# DOUT.net
KiCad netlist of a schematic drawn in EAGLE
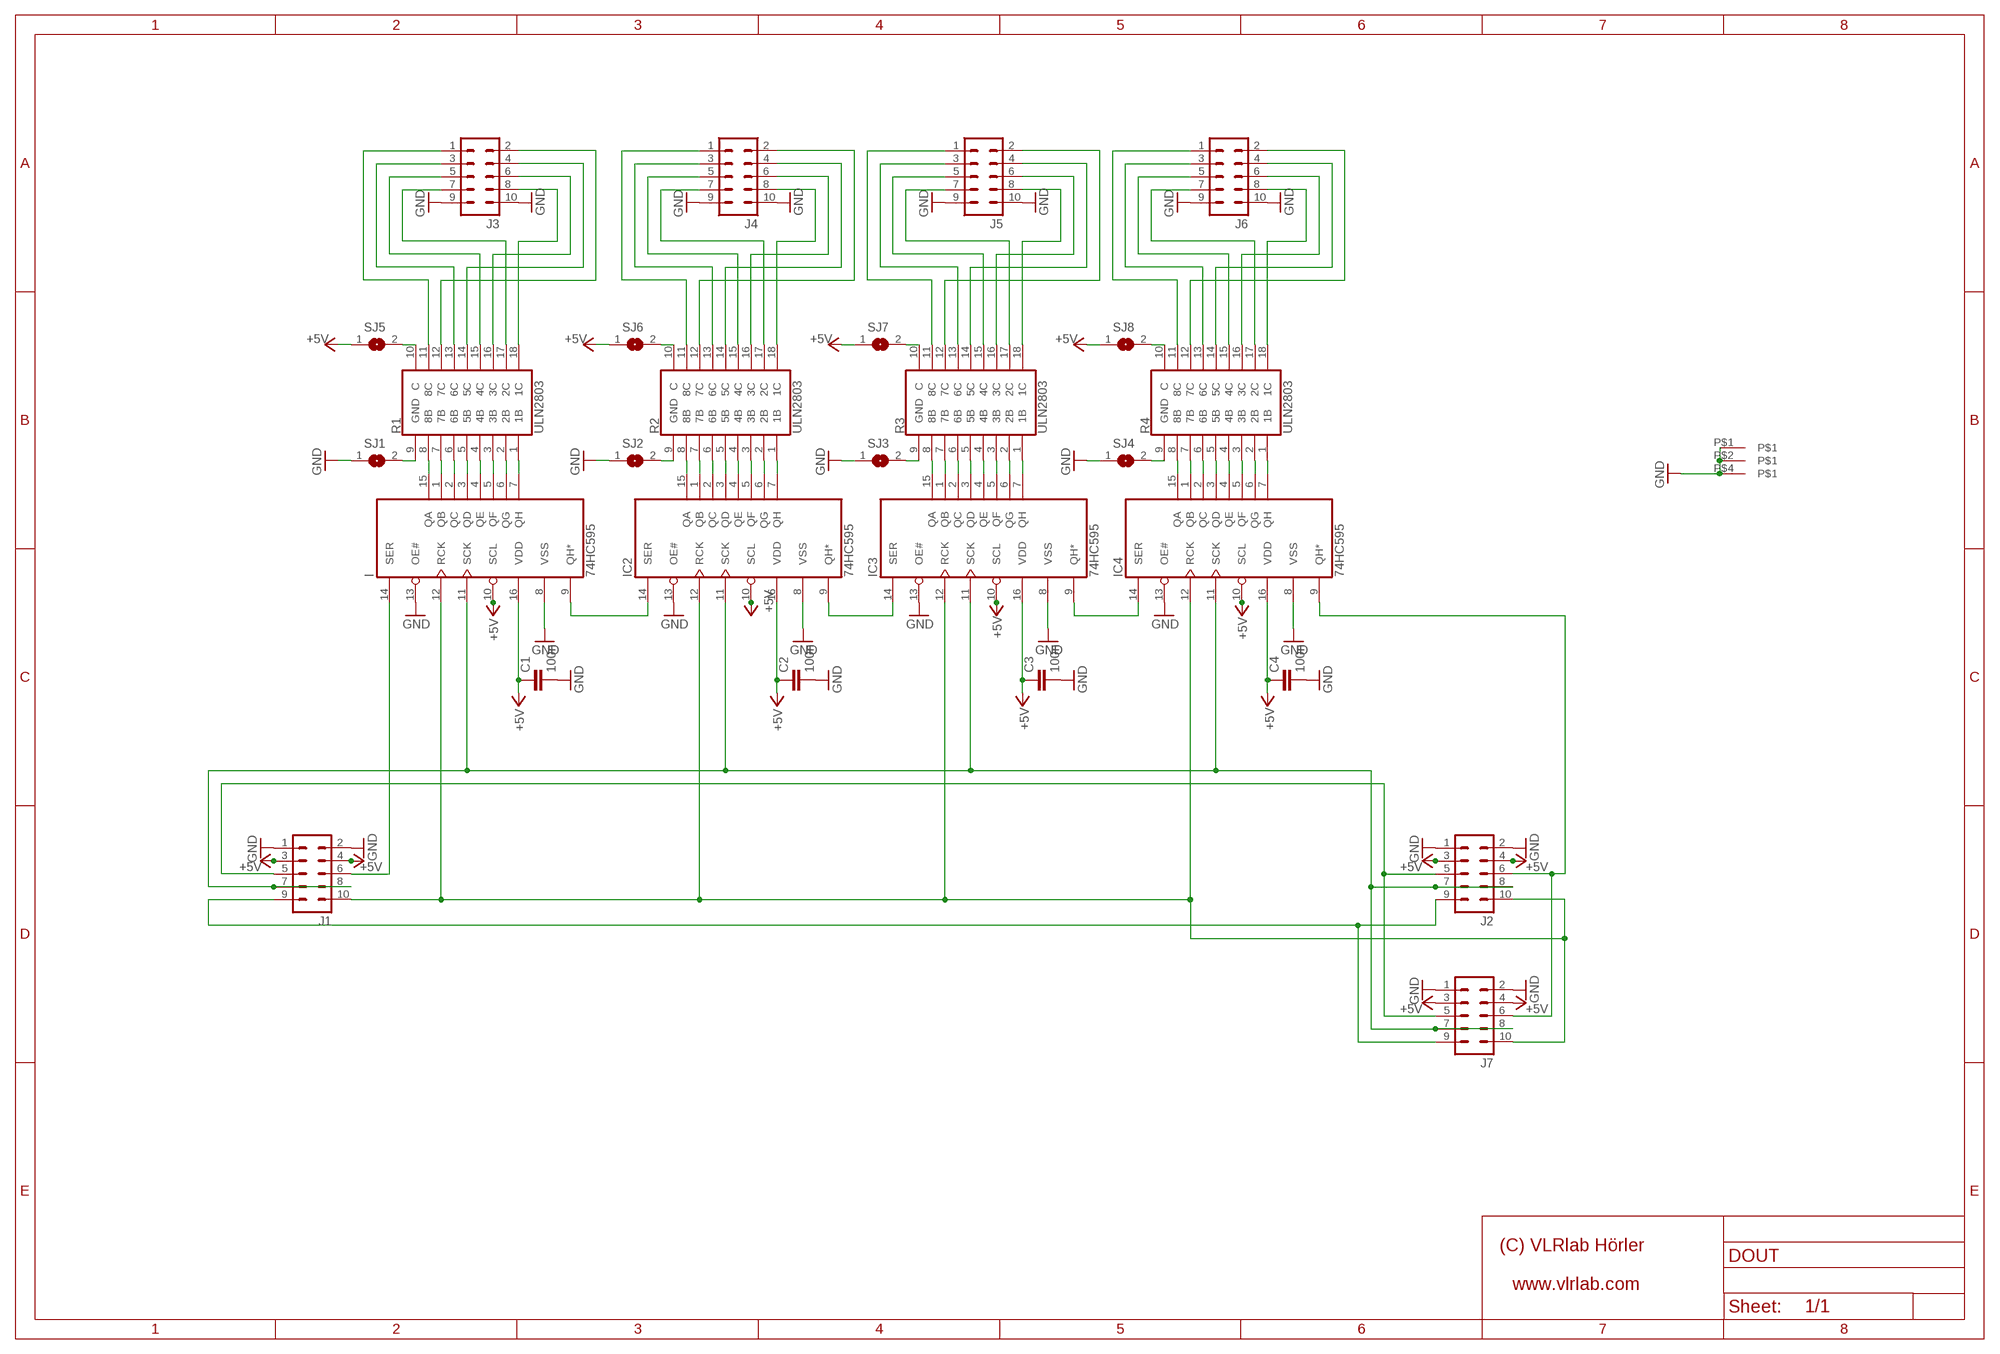
[diagram p0: schematic, sheet 1]

(export (version "E")
  (design (tool "Eeschema 10.0.6"))
  (components
    (comp (ref "C1")
      (value "100n")
      (footprint "eagle-import:C025-025X050")
      (libsource (lib "eagle-import") (part "C-EU025-025X050"))
    )
    (comp (ref "C2")
      (value "100n")
      (footprint "eagle-import:C025-025X050")
      (libsource (lib "eagle-import") (part "C-EU025-025X050"))
    )
    (comp (ref "C3")
      (value "100n")
      (footprint "eagle-import:C025-025X050")
      (libsource (lib "eagle-import") (part "C-EU025-025X050"))
    )
    (comp (ref "C4")
      (value "100n")
      (footprint "eagle-import:C025-025X050")
      (libsource (lib "eagle-import") (part "C-EU025-025X050"))
    )
    (comp (ref "I")
      (value "74HC595")
      (footprint "eagle-import:DIL16")
      (libsource (lib "eagle-import") (part "74HC595DIP16"))
    )
    (comp (ref "IC2")
      (value "74HC595")
      (footprint "eagle-import:DIL16")
      (libsource (lib "eagle-import") (part "74HC595DIP16"))
    )
    (comp (ref "IC3")
      (value "74HC595")
      (footprint "eagle-import:DIL16")
      (libsource (lib "eagle-import") (part "74HC595DIP16"))
    )
    (comp (ref "IC4")
      (value "74HC595")
      (footprint "eagle-import:DIL16")
      (libsource (lib "eagle-import") (part "74HC595DIP16"))
    )
    (comp (ref "J1")
      (value "ML10")
      (footprint "eagle-import:ML10")
      (libsource (lib "eagle-import") (part "ML10"))
    )
    (comp (ref "J2")
      (value "ML10")
      (footprint "eagle-import:ML10")
      (libsource (lib "eagle-import") (part "ML10"))
    )
    (comp (ref "J3")
      (value "ML10")
      (footprint "eagle-import:ML10")
      (libsource (lib "eagle-import") (part "ML10"))
    )
    (comp (ref "J4")
      (value "ML10")
      (footprint "eagle-import:ML10")
      (libsource (lib "eagle-import") (part "ML10"))
    )
    (comp (ref "J5")
      (value "ML10")
      (footprint "eagle-import:ML10")
      (libsource (lib "eagle-import") (part "ML10"))
    )
    (comp (ref "J6")
      (value "ML10")
      (footprint "eagle-import:ML10")
      (libsource (lib "eagle-import") (part "ML10"))
    )
    (comp (ref "J7")
      (value "ML10")
      (footprint "eagle-import:ML10")
      (libsource (lib "eagle-import") (part "ML10"))
    )
    (comp (ref "R1")
      (value "ULN2803")
      (footprint "eagle-import:DIL18")
      (libsource (lib "eagle-import") (part "ULN2803"))
    )
    (comp (ref "R2")
      (value "ULN2803")
      (footprint "eagle-import:DIL18")
      (libsource (lib "eagle-import") (part "ULN2803"))
    )
    (comp (ref "R3")
      (value "ULN2803")
      (footprint "eagle-import:DIL18")
      (libsource (lib "eagle-import") (part "ULN2803"))
    )
    (comp (ref "R4")
      (value "ULN2803")
      (footprint "eagle-import:DIL18")
      (libsource (lib "eagle-import") (part "ULN2803"))
    )
    (comp (ref "SJ1") (value "SJ") (footprint "eagle-import:SJ") (libsource (lib "eagle-import") (part "SJ")))
    (comp (ref "SJ2") (value "SJ") (footprint "eagle-import:SJ") (libsource (lib "eagle-import") (part "SJ")))
    (comp (ref "SJ3") (value "SJ") (footprint "eagle-import:SJ") (libsource (lib "eagle-import") (part "SJ")))
    (comp (ref "SJ4") (value "SJ") (footprint "eagle-import:SJ") (libsource (lib "eagle-import") (part "SJ")))
    (comp (ref "SJ5") (value "SJ") (footprint "eagle-import:SJ") (libsource (lib "eagle-import") (part "SJ")))
    (comp (ref "SJ6") (value "SJ") (footprint "eagle-import:SJ") (libsource (lib "eagle-import") (part "SJ")))
    (comp (ref "SJ7") (value "SJ") (footprint "eagle-import:SJ") (libsource (lib "eagle-import") (part "SJ")))
    (comp (ref "SJ8") (value "SJ") (footprint "eagle-import:SJ") (libsource (lib "eagle-import") (part "SJ")))
    (comp (ref "U$7")
      (value "MIDIBOX_HALF")
      (footprint "eagle-import:MIDIBOX14X6")
      (libsource (lib "eagle-import") (part "MIDIBOX_HALF"))
    )
  )
  (nets
    (net (code "1") (name "+5V") (class "Default")
      (node (ref "C1") (pin "1") (pinfunction "1_1") (pintype "passive"))
      (node (ref "C2") (pin "1") (pinfunction "1_1") (pintype "passive"))
      (node (ref "C3") (pin "1") (pinfunction "1_1") (pintype "passive"))
      (node (ref "C4") (pin "1") (pinfunction "1_1") (pintype "passive"))
      (node (ref "I") (pin "10") (pinfunction "SCL_10") (pintype "input"))
      (node (ref "I") (pin "16") (pinfunction "VDD_16") (pintype "power_in"))
      (node (ref "IC2") (pin "10") (pinfunction "SCL_10") (pintype "input"))
      (node (ref "IC2") (pin "16") (pinfunction "VDD_16") (pintype "power_in"))
      (node (ref "IC3") (pin "10") (pinfunction "SCL_10") (pintype "input"))
      (node (ref "IC3") (pin "16") (pinfunction "VDD_16") (pintype "power_in"))
      (node (ref "IC4") (pin "10") (pinfunction "SCL_10") (pintype "input"))
      (node (ref "IC4") (pin "16") (pinfunction "VDD_16") (pintype "power_in"))
      (node (ref "J1") (pin "3") (pinfunction "3_3") (pintype "passive"))
      (node (ref "J1") (pin "4") (pinfunction "4_4") (pintype "passive"))
      (node (ref "J2") (pin "3") (pinfunction "3_3") (pintype "passive"))
      (node (ref "J2") (pin "4") (pinfunction "4_4") (pintype "passive"))
      (node (ref "J7") (pin "3") (pinfunction "3_3") (pintype "passive"))
      (node (ref "J7") (pin "4") (pinfunction "4_4") (pintype "passive"))
      (node (ref "SJ5") (pin "1") (pinfunction "1_1") (pintype "passive"))
      (node (ref "SJ6") (pin "1") (pinfunction "1_1") (pintype "passive"))
      (node (ref "SJ7") (pin "1") (pinfunction "1_1") (pintype "passive"))
      (node (ref "SJ8") (pin "1") (pinfunction "1_1") (pintype "passive"))
    )
    (net (code "2") (name "GND") (class "Default")
      (node (ref "C1") (pin "2") (pinfunction "2_2") (pintype "passive"))
      (node (ref "C2") (pin "2") (pinfunction "2_2") (pintype "passive"))
      (node (ref "C3") (pin "2") (pinfunction "2_2") (pintype "passive"))
      (node (ref "C4") (pin "2") (pinfunction "2_2") (pintype "passive"))
      (node (ref "I") (pin "13") (pinfunction "OE#_13") (pintype "input"))
      (node (ref "I") (pin "8") (pinfunction "VSS_8") (pintype "power_in"))
      (node (ref "IC2") (pin "13") (pinfunction "OE#_13") (pintype "input"))
      (node (ref "IC2") (pin "8") (pinfunction "VSS_8") (pintype "power_in"))
      (node (ref "IC3") (pin "13") (pinfunction "OE#_13") (pintype "input"))
      (node (ref "IC3") (pin "8") (pinfunction "VSS_8") (pintype "power_in"))
      (node (ref "IC4") (pin "13") (pinfunction "OE#_13") (pintype "input"))
      (node (ref "IC4") (pin "8") (pinfunction "VSS_8") (pintype "power_in"))
      (node (ref "J1") (pin "1") (pinfunction "1_1") (pintype "passive"))
      (node (ref "J1") (pin "2") (pinfunction "2_2") (pintype "passive"))
      (node (ref "J2") (pin "1") (pinfunction "1_1") (pintype "passive"))
      (node (ref "J2") (pin "2") (pinfunction "2_2") (pintype "passive"))
      (node (ref "J3") (pin "10") (pinfunction "10_10") (pintype "passive"))
      (node (ref "J3") (pin "9") (pinfunction "9_9") (pintype "passive"))
      (node (ref "J4") (pin "10") (pinfunction "10_10") (pintype "passive"))
      (node (ref "J4") (pin "9") (pinfunction "9_9") (pintype "passive"))
      (node (ref "J5") (pin "10") (pinfunction "10_10") (pintype "passive"))
      (node (ref "J5") (pin "9") (pinfunction "9_9") (pintype "passive"))
      (node (ref "J6") (pin "10") (pinfunction "10_10") (pintype "passive"))
      (node (ref "J6") (pin "9") (pinfunction "9_9") (pintype "passive"))
      (node (ref "J7") (pin "1") (pinfunction "1_1") (pintype "passive"))
      (node (ref "J7") (pin "2") (pinfunction "2_2") (pintype "passive"))
      (node (ref "SJ1") (pin "1") (pinfunction "1_1") (pintype "passive"))
      (node (ref "SJ2") (pin "1") (pinfunction "1_1") (pintype "passive"))
      (node (ref "SJ3") (pin "1") (pinfunction "1_1") (pintype "passive"))
      (node (ref "SJ4") (pin "1") (pinfunction "1_1") (pintype "passive"))
      (node (ref "U$7") (pin "P$1") (pinfunction "P$1_P$1") (pintype "bidirectional"))
      (node (ref "U$7") (pin "P$2") (pinfunction "P$1_P$2") (pintype "bidirectional"))
      (node (ref "U$7") (pin "P$4") (pinfunction "P$1_P$4") (pintype "bidirectional"))
    )
    (net (code "3") (name "Net-(I-QA)") (class "Default")
      (node (ref "I") (pin "15") (pinfunction "QA_15") (pintype "tri_state"))
      (node (ref "R1") (pin "8") (pinfunction "8B_8") (pintype "input"))
    )
    (net (code "4") (name "Net-(I-QB)") (class "Default")
      (node (ref "I") (pin "1") (pinfunction "QB_1") (pintype "tri_state"))
      (node (ref "R1") (pin "7") (pinfunction "7B_7") (pintype "input"))
    )
    (net (code "5") (name "Net-(I-QC)") (class "Default")
      (node (ref "I") (pin "2") (pinfunction "QC_2") (pintype "tri_state"))
      (node (ref "R1") (pin "6") (pinfunction "6B_6") (pintype "input"))
    )
    (net (code "6") (name "Net-(I-QD)") (class "Default")
      (node (ref "I") (pin "3") (pinfunction "QD_3") (pintype "tri_state"))
      (node (ref "R1") (pin "5") (pinfunction "5B_5") (pintype "input"))
    )
    (net (code "7") (name "Net-(I-QE)") (class "Default")
      (node (ref "I") (pin "4") (pinfunction "QE_4") (pintype "tri_state"))
      (node (ref "R1") (pin "4") (pinfunction "4B_4") (pintype "input"))
    )
    (net (code "8") (name "Net-(I-QF)") (class "Default")
      (node (ref "I") (pin "5") (pinfunction "QF_5") (pintype "tri_state"))
      (node (ref "R1") (pin "3") (pinfunction "3B_3") (pintype "input"))
    )
    (net (code "9") (name "Net-(I-QG)") (class "Default")
      (node (ref "I") (pin "6") (pinfunction "QG_6") (pintype "tri_state"))
      (node (ref "R1") (pin "2") (pinfunction "2B_2") (pintype "input"))
    )
    (net (code "10") (name "Net-(I-QH)") (class "Default")
      (node (ref "I") (pin "7") (pinfunction "QH_7") (pintype "tri_state"))
      (node (ref "R1") (pin "1") (pinfunction "1B_1") (pintype "input"))
    )
    (net (code "11") (name "Net-(I-QH*)") (class "Default")
      (node (ref "I") (pin "9") (pinfunction "QH*_9") (pintype "tri_state"))
      (node (ref "IC2") (pin "14") (pinfunction "SER_14") (pintype "input"))
    )
    (net (code "12") (name "Net-(I-RCK)") (class "Default")
      (node (ref "I") (pin "12") (pinfunction "RCK_12") (pintype "input"))
      (node (ref "IC2") (pin "12") (pinfunction "RCK_12") (pintype "input"))
      (node (ref "IC3") (pin "12") (pinfunction "RCK_12") (pintype "input"))
      (node (ref "IC4") (pin "12") (pinfunction "RCK_12") (pintype "input"))
      (node (ref "J1") (pin "10") (pinfunction "10_10") (pintype "passive"))
      (node (ref "J2") (pin "10") (pinfunction "10_10") (pintype "passive"))
      (node (ref "J7") (pin "10") (pinfunction "10_10") (pintype "passive"))
    )
    (net (code "13") (name "Net-(I-SCK)") (class "Default")
      (node (ref "I") (pin "11") (pinfunction "SCK_11") (pintype "input"))
      (node (ref "IC2") (pin "11") (pinfunction "SCK_11") (pintype "input"))
      (node (ref "IC3") (pin "11") (pinfunction "SCK_11") (pintype "input"))
      (node (ref "IC4") (pin "11") (pinfunction "SCK_11") (pintype "input"))
      (node (ref "J1") (pin "7") (pinfunction "7_7") (pintype "passive"))
      (node (ref "J1") (pin "8") (pinfunction "8_8") (pintype "passive"))
      (node (ref "J2") (pin "7") (pinfunction "7_7") (pintype "passive"))
      (node (ref "J2") (pin "8") (pinfunction "8_8") (pintype "passive"))
      (node (ref "J7") (pin "7") (pinfunction "7_7") (pintype "passive"))
      (node (ref "J7") (pin "8") (pinfunction "8_8") (pintype "passive"))
    )
    (net (code "14") (name "Net-(I-SER)") (class "Default")
      (node (ref "I") (pin "14") (pinfunction "SER_14") (pintype "input"))
      (node (ref "J1") (pin "6") (pinfunction "6_6") (pintype "passive"))
    )
    (net (code "15") (name "Net-(IC2-QA)") (class "Default")
      (node (ref "IC2") (pin "15") (pinfunction "QA_15") (pintype "tri_state"))
      (node (ref "R2") (pin "8") (pinfunction "8B_8") (pintype "input"))
    )
    (net (code "16") (name "Net-(IC2-QB)") (class "Default")
      (node (ref "IC2") (pin "1") (pinfunction "QB_1") (pintype "tri_state"))
      (node (ref "R2") (pin "7") (pinfunction "7B_7") (pintype "input"))
    )
    (net (code "17") (name "Net-(IC2-QC)") (class "Default")
      (node (ref "IC2") (pin "2") (pinfunction "QC_2") (pintype "tri_state"))
      (node (ref "R2") (pin "6") (pinfunction "6B_6") (pintype "input"))
    )
    (net (code "18") (name "Net-(IC2-QD)") (class "Default")
      (node (ref "IC2") (pin "3") (pinfunction "QD_3") (pintype "tri_state"))
      (node (ref "R2") (pin "5") (pinfunction "5B_5") (pintype "input"))
    )
    (net (code "19") (name "Net-(IC2-QE)") (class "Default")
      (node (ref "IC2") (pin "4") (pinfunction "QE_4") (pintype "tri_state"))
      (node (ref "R2") (pin "4") (pinfunction "4B_4") (pintype "input"))
    )
    (net (code "20") (name "Net-(IC2-QF)") (class "Default")
      (node (ref "IC2") (pin "5") (pinfunction "QF_5") (pintype "tri_state"))
      (node (ref "R2") (pin "3") (pinfunction "3B_3") (pintype "input"))
    )
    (net (code "21") (name "Net-(IC2-QG)") (class "Default")
      (node (ref "IC2") (pin "6") (pinfunction "QG_6") (pintype "tri_state"))
      (node (ref "R2") (pin "2") (pinfunction "2B_2") (pintype "input"))
    )
    (net (code "22") (name "Net-(IC2-QH)") (class "Default")
      (node (ref "IC2") (pin "7") (pinfunction "QH_7") (pintype "tri_state"))
      (node (ref "R2") (pin "1") (pinfunction "1B_1") (pintype "input"))
    )
    (net (code "23") (name "Net-(IC2-QH*)") (class "Default")
      (node (ref "IC2") (pin "9") (pinfunction "QH*_9") (pintype "tri_state"))
      (node (ref "IC3") (pin "14") (pinfunction "SER_14") (pintype "input"))
    )
    (net (code "24") (name "Net-(IC3-QA)") (class "Default")
      (node (ref "IC3") (pin "15") (pinfunction "QA_15") (pintype "tri_state"))
      (node (ref "R3") (pin "8") (pinfunction "8B_8") (pintype "input"))
    )
    (net (code "25") (name "Net-(IC3-QB)") (class "Default")
      (node (ref "IC3") (pin "1") (pinfunction "QB_1") (pintype "tri_state"))
      (node (ref "R3") (pin "7") (pinfunction "7B_7") (pintype "input"))
    )
    (net (code "26") (name "Net-(IC3-QC)") (class "Default")
      (node (ref "IC3") (pin "2") (pinfunction "QC_2") (pintype "tri_state"))
      (node (ref "R3") (pin "6") (pinfunction "6B_6") (pintype "input"))
    )
    (net (code "27") (name "Net-(IC3-QD)") (class "Default")
      (node (ref "IC3") (pin "3") (pinfunction "QD_3") (pintype "tri_state"))
      (node (ref "R3") (pin "5") (pinfunction "5B_5") (pintype "input"))
    )
    (net (code "28") (name "Net-(IC3-QE)") (class "Default")
      (node (ref "IC3") (pin "4") (pinfunction "QE_4") (pintype "tri_state"))
      (node (ref "R3") (pin "4") (pinfunction "4B_4") (pintype "input"))
    )
    (net (code "29") (name "Net-(IC3-QF)") (class "Default")
      (node (ref "IC3") (pin "5") (pinfunction "QF_5") (pintype "tri_state"))
      (node (ref "R3") (pin "3") (pinfunction "3B_3") (pintype "input"))
    )
    (net (code "30") (name "Net-(IC3-QG)") (class "Default")
      (node (ref "IC3") (pin "6") (pinfunction "QG_6") (pintype "tri_state"))
      (node (ref "R3") (pin "2") (pinfunction "2B_2") (pintype "input"))
    )
    (net (code "31") (name "Net-(IC3-QH)") (class "Default")
      (node (ref "IC3") (pin "7") (pinfunction "QH_7") (pintype "tri_state"))
      (node (ref "R3") (pin "1") (pinfunction "1B_1") (pintype "input"))
    )
    (net (code "32") (name "Net-(IC3-QH*)") (class "Default")
      (node (ref "IC3") (pin "9") (pinfunction "QH*_9") (pintype "tri_state"))
      (node (ref "IC4") (pin "14") (pinfunction "SER_14") (pintype "input"))
    )
    (net (code "33") (name "Net-(IC4-QA)") (class "Default")
      (node (ref "IC4") (pin "15") (pinfunction "QA_15") (pintype "tri_state"))
      (node (ref "R4") (pin "8") (pinfunction "8B_8") (pintype "input"))
    )
    (net (code "34") (name "Net-(IC4-QB)") (class "Default")
      (node (ref "IC4") (pin "1") (pinfunction "QB_1") (pintype "tri_state"))
      (node (ref "R4") (pin "7") (pinfunction "7B_7") (pintype "input"))
    )
    (net (code "35") (name "Net-(IC4-QC)") (class "Default")
      (node (ref "IC4") (pin "2") (pinfunction "QC_2") (pintype "tri_state"))
      (node (ref "R4") (pin "6") (pinfunction "6B_6") (pintype "input"))
    )
    (net (code "36") (name "Net-(IC4-QD)") (class "Default")
      (node (ref "IC4") (pin "3") (pinfunction "QD_3") (pintype "tri_state"))
      (node (ref "R4") (pin "5") (pinfunction "5B_5") (pintype "input"))
    )
    (net (code "37") (name "Net-(IC4-QE)") (class "Default")
      (node (ref "IC4") (pin "4") (pinfunction "QE_4") (pintype "tri_state"))
      (node (ref "R4") (pin "4") (pinfunction "4B_4") (pintype "input"))
    )
    (net (code "38") (name "Net-(IC4-QF)") (class "Default")
      (node (ref "IC4") (pin "5") (pinfunction "QF_5") (pintype "tri_state"))
      (node (ref "R4") (pin "3") (pinfunction "3B_3") (pintype "input"))
    )
    (net (code "39") (name "Net-(IC4-QG)") (class "Default")
      (node (ref "IC4") (pin "6") (pinfunction "QG_6") (pintype "tri_state"))
      (node (ref "R4") (pin "2") (pinfunction "2B_2") (pintype "input"))
    )
    (net (code "40") (name "Net-(IC4-QH)") (class "Default")
      (node (ref "IC4") (pin "7") (pinfunction "QH_7") (pintype "tri_state"))
      (node (ref "R4") (pin "1") (pinfunction "1B_1") (pintype "input"))
    )
    (net (code "41") (name "Net-(IC4-QH*)") (class "Default")
      (node (ref "IC4") (pin "9") (pinfunction "QH*_9") (pintype "tri_state"))
      (node (ref "J2") (pin "6") (pinfunction "6_6") (pintype "passive"))
      (node (ref "J7") (pin "6") (pinfunction "6_6") (pintype "passive"))
    )
    (net (code "42") (name "Net-(J1-Pad5)") (class "Default")
      (node (ref "J1") (pin "5") (pinfunction "5_5") (pintype "passive"))
      (node (ref "J2") (pin "5") (pinfunction "5_5") (pintype "passive"))
      (node (ref "J7") (pin "5") (pinfunction "5_5") (pintype "passive"))
    )
    (net (code "43") (name "Net-(J1-Pad9)") (class "Default")
      (node (ref "J1") (pin "9") (pinfunction "9_9") (pintype "passive"))
      (node (ref "J2") (pin "9") (pinfunction "9_9") (pintype "passive"))
      (node (ref "J7") (pin "9") (pinfunction "9_9") (pintype "passive"))
    )
    (net (code "44") (name "Net-(R1-1C)") (class "Default")
      (node (ref "J3") (pin "8") (pinfunction "8_8") (pintype "passive"))
      (node (ref "R1") (pin "18") (pinfunction "1C_18") (pintype "open_collector"))
    )
    (net (code "45") (name "Net-(R1-2C)") (class "Default")
      (node (ref "J3") (pin "7") (pinfunction "7_7") (pintype "passive"))
      (node (ref "R1") (pin "17") (pinfunction "2C_17") (pintype "open_collector"))
    )
    (net (code "46") (name "Net-(R1-3C)") (class "Default")
      (node (ref "J3") (pin "6") (pinfunction "6_6") (pintype "passive"))
      (node (ref "R1") (pin "16") (pinfunction "3C_16") (pintype "open_collector"))
    )
    (net (code "47") (name "Net-(R1-4C)") (class "Default")
      (node (ref "J3") (pin "5") (pinfunction "5_5") (pintype "passive"))
      (node (ref "R1") (pin "15") (pinfunction "4C_15") (pintype "open_collector"))
    )
    (net (code "48") (name "Net-(R1-5C)") (class "Default")
      (node (ref "J3") (pin "4") (pinfunction "4_4") (pintype "passive"))
      (node (ref "R1") (pin "14") (pinfunction "5C_14") (pintype "open_collector"))
    )
    (net (code "49") (name "Net-(R1-6C)") (class "Default")
      (node (ref "J3") (pin "3") (pinfunction "3_3") (pintype "passive"))
      (node (ref "R1") (pin "13") (pinfunction "6C_13") (pintype "open_collector"))
    )
    (net (code "50") (name "Net-(R1-7C)") (class "Default")
      (node (ref "J3") (pin "2") (pinfunction "2_2") (pintype "passive"))
      (node (ref "R1") (pin "12") (pinfunction "7C_12") (pintype "open_collector"))
    )
    (net (code "51") (name "Net-(R1-8C)") (class "Default")
      (node (ref "J3") (pin "1") (pinfunction "1_1") (pintype "passive"))
      (node (ref "R1") (pin "11") (pinfunction "8C_11") (pintype "open_collector"))
    )
    (net (code "52") (name "Net-(R1-C)") (class "Default")
      (node (ref "R1") (pin "10") (pinfunction "C_10") (pintype "passive"))
      (node (ref "SJ5") (pin "2") (pinfunction "2_2") (pintype "passive"))
    )
    (net (code "53") (name "Net-(R1-GND)") (class "Default")
      (node (ref "R1") (pin "9") (pinfunction "GND_9") (pintype "power_in"))
      (node (ref "SJ1") (pin "2") (pinfunction "2_2") (pintype "passive"))
    )
    (net (code "54") (name "Net-(R2-1C)") (class "Default")
      (node (ref "J4") (pin "8") (pinfunction "8_8") (pintype "passive"))
      (node (ref "R2") (pin "18") (pinfunction "1C_18") (pintype "open_collector"))
    )
    (net (code "55") (name "Net-(R2-2C)") (class "Default")
      (node (ref "J4") (pin "7") (pinfunction "7_7") (pintype "passive"))
      (node (ref "R2") (pin "17") (pinfunction "2C_17") (pintype "open_collector"))
    )
    (net (code "56") (name "Net-(R2-3C)") (class "Default")
      (node (ref "J4") (pin "6") (pinfunction "6_6") (pintype "passive"))
      (node (ref "R2") (pin "16") (pinfunction "3C_16") (pintype "open_collector"))
    )
    (net (code "57") (name "Net-(R2-4C)") (class "Default")
      (node (ref "J4") (pin "5") (pinfunction "5_5") (pintype "passive"))
      (node (ref "R2") (pin "15") (pinfunction "4C_15") (pintype "open_collector"))
    )
    (net (code "58") (name "Net-(R2-5C)") (class "Default")
      (node (ref "J4") (pin "4") (pinfunction "4_4") (pintype "passive"))
      (node (ref "R2") (pin "14") (pinfunction "5C_14") (pintype "open_collector"))
    )
    (net (code "59") (name "Net-(R2-6C)") (class "Default")
      (node (ref "J4") (pin "3") (pinfunction "3_3") (pintype "passive"))
      (node (ref "R2") (pin "13") (pinfunction "6C_13") (pintype "open_collector"))
    )
    (net (code "60") (name "Net-(R2-7C)") (class "Default")
      (node (ref "J4") (pin "2") (pinfunction "2_2") (pintype "passive"))
      (node (ref "R2") (pin "12") (pinfunction "7C_12") (pintype "open_collector"))
    )
    (net (code "61") (name "Net-(R2-8C)") (class "Default")
      (node (ref "J4") (pin "1") (pinfunction "1_1") (pintype "passive"))
      (node (ref "R2") (pin "11") (pinfunction "8C_11") (pintype "open_collector"))
    )
    (net (code "62") (name "Net-(R2-C)") (class "Default")
      (node (ref "R2") (pin "10") (pinfunction "C_10") (pintype "passive"))
      (node (ref "SJ6") (pin "2") (pinfunction "2_2") (pintype "passive"))
    )
    (net (code "63") (name "Net-(R2-GND)") (class "Default")
      (node (ref "R2") (pin "9") (pinfunction "GND_9") (pintype "power_in"))
      (node (ref "SJ2") (pin "2") (pinfunction "2_2") (pintype "passive"))
    )
    (net (code "64") (name "Net-(R3-1C)") (class "Default")
      (node (ref "J5") (pin "8") (pinfunction "8_8") (pintype "passive"))
      (node (ref "R3") (pin "18") (pinfunction "1C_18") (pintype "open_collector"))
    )
    (net (code "65") (name "Net-(R3-2C)") (class "Default")
      (node (ref "J5") (pin "7") (pinfunction "7_7") (pintype "passive"))
      (node (ref "R3") (pin "17") (pinfunction "2C_17") (pintype "open_collector"))
    )
    (net (code "66") (name "Net-(R3-3C)") (class "Default")
      (node (ref "J5") (pin "6") (pinfunction "6_6") (pintype "passive"))
      (node (ref "R3") (pin "16") (pinfunction "3C_16") (pintype "open_collector"))
    )
    (net (code "67") (name "Net-(R3-4C)") (class "Default")
      (node (ref "J5") (pin "5") (pinfunction "5_5") (pintype "passive"))
      (node (ref "R3") (pin "15") (pinfunction "4C_15") (pintype "open_collector"))
    )
    (net (code "68") (name "Net-(R3-5C)") (class "Default")
      (node (ref "J5") (pin "4") (pinfunction "4_4") (pintype "passive"))
      (node (ref "R3") (pin "14") (pinfunction "5C_14") (pintype "open_collector"))
    )
    (net (code "69") (name "Net-(R3-6C)") (class "Default")
      (node (ref "J5") (pin "3") (pinfunction "3_3") (pintype "passive"))
      (node (ref "R3") (pin "13") (pinfunction "6C_13") (pintype "open_collector"))
    )
    (net (code "70") (name "Net-(R3-7C)") (class "Default")
      (node (ref "J5") (pin "2") (pinfunction "2_2") (pintype "passive"))
      (node (ref "R3") (pin "12") (pinfunction "7C_12") (pintype "open_collector"))
    )
    (net (code "71") (name "Net-(R3-8C)") (class "Default")
      (node (ref "J5") (pin "1") (pinfunction "1_1") (pintype "passive"))
      (node (ref "R3") (pin "11") (pinfunction "8C_11") (pintype "open_collector"))
    )
    (net (code "72") (name "Net-(R3-C)") (class "Default")
      (node (ref "R3") (pin "10") (pinfunction "C_10") (pintype "passive"))
      (node (ref "SJ7") (pin "2") (pinfunction "2_2") (pintype "passive"))
    )
    (net (code "73") (name "Net-(R3-GND)") (class "Default")
      (node (ref "R3") (pin "9") (pinfunction "GND_9") (pintype "power_in"))
      (node (ref "SJ3") (pin "2") (pinfunction "2_2") (pintype "passive"))
    )
    (net (code "74") (name "Net-(R4-1C)") (class "Default")
      (node (ref "J6") (pin "8") (pinfunction "8_8") (pintype "passive"))
      (node (ref "R4") (pin "18") (pinfunction "1C_18") (pintype "open_collector"))
    )
    (net (code "75") (name "Net-(R4-2C)") (class "Default")
      (node (ref "J6") (pin "7") (pinfunction "7_7") (pintype "passive"))
      (node (ref "R4") (pin "17") (pinfunction "2C_17") (pintype "open_collector"))
    )
    (net (code "76") (name "Net-(R4-3C)") (class "Default")
      (node (ref "J6") (pin "6") (pinfunction "6_6") (pintype "passive"))
      (node (ref "R4") (pin "16") (pinfunction "3C_16") (pintype "open_collector"))
    )
    (net (code "77") (name "Net-(R4-4C)") (class "Default")
      (node (ref "J6") (pin "5") (pinfunction "5_5") (pintype "passive"))
      (node (ref "R4") (pin "15") (pinfunction "4C_15") (pintype "open_collector"))
    )
    (net (code "78") (name "Net-(R4-5C)") (class "Default")
      (node (ref "J6") (pin "4") (pinfunction "4_4") (pintype "passive"))
      (node (ref "R4") (pin "14") (pinfunction "5C_14") (pintype "open_collector"))
    )
    (net (code "79") (name "Net-(R4-6C)") (class "Default")
      (node (ref "J6") (pin "3") (pinfunction "3_3") (pintype "passive"))
      (node (ref "R4") (pin "13") (pinfunction "6C_13") (pintype "open_collector"))
    )
    (net (code "80") (name "Net-(R4-7C)") (class "Default")
      (node (ref "J6") (pin "2") (pinfunction "2_2") (pintype "passive"))
      (node (ref "R4") (pin "12") (pinfunction "7C_12") (pintype "open_collector"))
    )
    (net (code "81") (name "Net-(R4-8C)") (class "Default")
      (node (ref "J6") (pin "1") (pinfunction "1_1") (pintype "passive"))
      (node (ref "R4") (pin "11") (pinfunction "8C_11") (pintype "open_collector"))
    )
    (net (code "82") (name "Net-(R4-C)") (class "Default")
      (node (ref "R4") (pin "10") (pinfunction "C_10") (pintype "passive"))
      (node (ref "SJ8") (pin "2") (pinfunction "2_2") (pintype "passive"))
    )
    (net (code "83") (name "Net-(R4-GND)") (class "Default")
      (node (ref "R4") (pin "9") (pinfunction "GND_9") (pintype "power_in"))
      (node (ref "SJ4") (pin "2") (pinfunction "2_2") (pintype "passive"))
    )
  )
)
